# 6waydistro.net
KiCad netlist of a schematic drawn in EAGLE
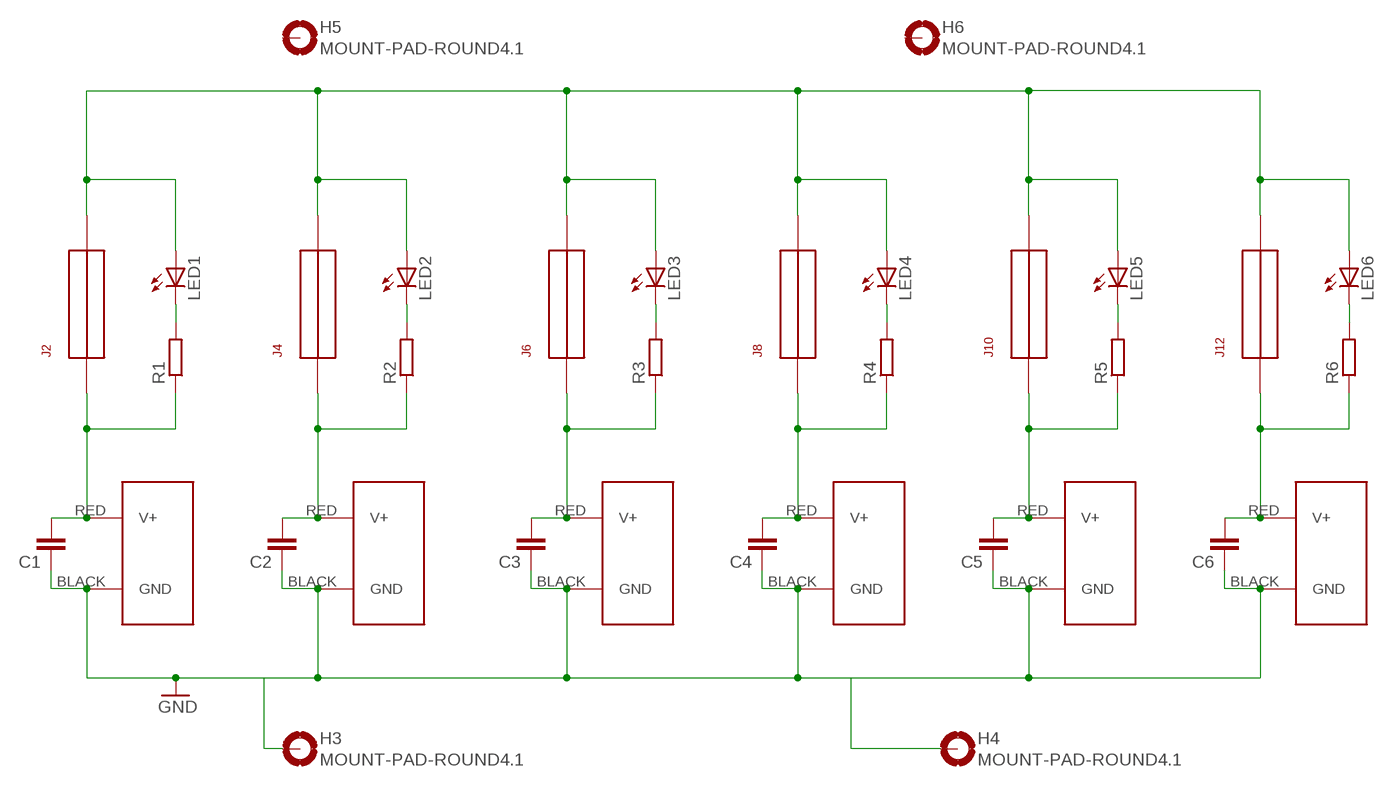
[diagram p0: schematic, sheet 1]

(export (version "E")
  (design (tool "Eeschema 10.0.6"))
  (components
    (comp (ref "C1")
      (value "C-EU050-025X075")
      (footprint "eagle-import:C050-025X075")
      (libsource (lib "eagle-import") (part "C-EU050-025X075"))
    )
    (comp (ref "C2")
      (value "C-EU050-025X075")
      (footprint "eagle-import:C050-025X075")
      (libsource (lib "eagle-import") (part "C-EU050-025X075"))
    )
    (comp (ref "C3")
      (value "C-EU050-025X075")
      (footprint "eagle-import:C050-025X075")
      (libsource (lib "eagle-import") (part "C-EU050-025X075"))
    )
    (comp (ref "C4")
      (value "C-EU050-025X075")
      (footprint "eagle-import:C050-025X075")
      (libsource (lib "eagle-import") (part "C-EU050-025X075"))
    )
    (comp (ref "C5")
      (value "C-EU050-025X075")
      (footprint "eagle-import:C050-025X075")
      (libsource (lib "eagle-import") (part "C-EU050-025X075"))
    )
    (comp (ref "C6")
      (value "C-EU050-025X075")
      (footprint "eagle-import:C050-025X075")
      (libsource (lib "eagle-import") (part "C-EU050-025X075"))
    )
    (comp (ref "H3")
      (value "MOUNT-PAD-ROUND4.1")
      (footprint "eagle-import:4,1-PAD")
      (libsource (lib "eagle-import") (part "MOUNT-PAD-ROUND4.1"))
    )
    (comp (ref "H4")
      (value "MOUNT-PAD-ROUND4.1")
      (footprint "eagle-import:4,1-PAD")
      (libsource (lib "eagle-import") (part "MOUNT-PAD-ROUND4.1"))
    )
    (comp (ref "H5")
      (value "MOUNT-PAD-ROUND4.1")
      (footprint "eagle-import:4,1-PAD")
      (libsource (lib "eagle-import") (part "MOUNT-PAD-ROUND4.1"))
    )
    (comp (ref "H6")
      (value "MOUNT-PAD-ROUND4.1")
      (footprint "eagle-import:4,1-PAD")
      (libsource (lib "eagle-import") (part "MOUNT-PAD-ROUND4.1"))
    )
    (comp (ref "J1")
      (value "POWERPOLE_POWER45A")
      (footprint "eagle-import:POWERPOLE_PAIR_45A")
      (libsource (lib "eagle-import") (part "POWERPOLE_POWER45A"))
    )
    (comp (ref "J2")
      (value "FUSEATC")
      (footprint "eagle-import:FUSE_ATC")
      (libsource (lib "eagle-import") (part "FUSEATC"))
    )
    (comp (ref "J3")
      (value "POWERPOLE_POWER45A")
      (footprint "eagle-import:POWERPOLE_PAIR_45A")
      (libsource (lib "eagle-import") (part "POWERPOLE_POWER45A"))
    )
    (comp (ref "J4")
      (value "FUSEATC")
      (footprint "eagle-import:FUSE_ATC")
      (libsource (lib "eagle-import") (part "FUSEATC"))
    )
    (comp (ref "J5")
      (value "POWERPOLE_POWER45A")
      (footprint "eagle-import:POWERPOLE_PAIR_45A")
      (libsource (lib "eagle-import") (part "POWERPOLE_POWER45A"))
    )
    (comp (ref "J6")
      (value "FUSEATC")
      (footprint "eagle-import:FUSE_ATC")
      (libsource (lib "eagle-import") (part "FUSEATC"))
    )
    (comp (ref "J7")
      (value "POWERPOLE_POWER45A")
      (footprint "eagle-import:POWERPOLE_PAIR_45A")
      (libsource (lib "eagle-import") (part "POWERPOLE_POWER45A"))
    )
    (comp (ref "J8")
      (value "FUSEATC")
      (footprint "eagle-import:FUSE_ATC")
      (libsource (lib "eagle-import") (part "FUSEATC"))
    )
    (comp (ref "J9")
      (value "POWERPOLE_POWER45A")
      (footprint "eagle-import:POWERPOLE_PAIR_45A")
      (libsource (lib "eagle-import") (part "POWERPOLE_POWER45A"))
    )
    (comp (ref "J10")
      (value "FUSEATC")
      (footprint "eagle-import:FUSE_ATC")
      (libsource (lib "eagle-import") (part "FUSEATC"))
    )
    (comp (ref "J11")
      (value "POWERPOLE_POWER45A")
      (footprint "eagle-import:POWERPOLE_PAIR_45A")
      (libsource (lib "eagle-import") (part "POWERPOLE_POWER45A"))
    )
    (comp (ref "J12")
      (value "FUSEATC")
      (footprint "eagle-import:FUSE_ATC")
      (libsource (lib "eagle-import") (part "FUSEATC"))
    )
    (comp (ref "LED1")
      (value "LED3MM")
      (footprint "eagle-import:LED3MM")
      (libsource (lib "eagle-import") (part "LED3MM"))
    )
    (comp (ref "LED2")
      (value "LED3MM")
      (footprint "eagle-import:LED3MM")
      (libsource (lib "eagle-import") (part "LED3MM"))
    )
    (comp (ref "LED3")
      (value "LED3MM")
      (footprint "eagle-import:LED3MM")
      (libsource (lib "eagle-import") (part "LED3MM"))
    )
    (comp (ref "LED4")
      (value "LED3MM")
      (footprint "eagle-import:LED3MM")
      (libsource (lib "eagle-import") (part "LED3MM"))
    )
    (comp (ref "LED5")
      (value "LED3MM")
      (footprint "eagle-import:LED3MM")
      (libsource (lib "eagle-import") (part "LED3MM"))
    )
    (comp (ref "LED6")
      (value "LED3MM")
      (footprint "eagle-import:LED3MM")
      (libsource (lib "eagle-import") (part "LED3MM"))
    )
    (comp (ref "R1")
      (value "R-EU_0204/7")
      (footprint "eagle-import:0204_7")
      (libsource (lib "eagle-import") (part "R-EU_0204/7"))
    )
    (comp (ref "R2")
      (value "R-EU_0204/7")
      (footprint "eagle-import:0204_7")
      (libsource (lib "eagle-import") (part "R-EU_0204/7"))
    )
    (comp (ref "R3")
      (value "R-EU_0204/7")
      (footprint "eagle-import:0204_7")
      (libsource (lib "eagle-import") (part "R-EU_0204/7"))
    )
    (comp (ref "R4")
      (value "R-EU_0204/7")
      (footprint "eagle-import:0204_7")
      (libsource (lib "eagle-import") (part "R-EU_0204/7"))
    )
    (comp (ref "R5")
      (value "R-EU_0204/7")
      (footprint "eagle-import:0204_7")
      (libsource (lib "eagle-import") (part "R-EU_0204/7"))
    )
    (comp (ref "R6")
      (value "R-EU_0204/7")
      (footprint "eagle-import:0204_7")
      (libsource (lib "eagle-import") (part "R-EU_0204/7"))
    )
  )
  (nets
    (net (code "1") (name "GND") (class "Default")
      (node (ref "C1") (pin "1") (pinfunction "1_1") (pintype "passive"))
      (node (ref "C2") (pin "1") (pinfunction "1_1") (pintype "passive"))
      (node (ref "C3") (pin "1") (pinfunction "1_1") (pintype "passive"))
      (node (ref "C4") (pin "1") (pinfunction "1_1") (pintype "passive"))
      (node (ref "C5") (pin "1") (pinfunction "1_1") (pintype "passive"))
      (node (ref "C6") (pin "1") (pinfunction "1_1") (pintype "passive"))
      (node (ref "H3") (pin "B4,1") (pinfunction "MOUNT_B4,1") (pintype "passive"))
      (node (ref "H4") (pin "B4,1") (pinfunction "MOUNT_B4,1") (pintype "passive"))
      (node (ref "J1") (pin "BLACK") (pinfunction "GND_BLACK") (pintype "power_in"))
      (node (ref "J11") (pin "BLACK") (pinfunction "GND_BLACK") (pintype "power_in"))
      (node (ref "J3") (pin "BLACK") (pinfunction "GND_BLACK") (pintype "power_in"))
      (node (ref "J5") (pin "BLACK") (pinfunction "GND_BLACK") (pintype "power_in"))
      (node (ref "J7") (pin "BLACK") (pinfunction "GND_BLACK") (pintype "power_in"))
      (node (ref "J9") (pin "BLACK") (pinfunction "GND_BLACK") (pintype "power_in"))
    )
    (net (code "2") (name "Net-(J1-V+)") (class "Default")
      (node (ref "C1") (pin "2") (pinfunction "2_2") (pintype "passive"))
      (node (ref "J1") (pin "RED") (pinfunction "V+_RED") (pintype "power_in"))
      (node (ref "J2") (pin "P$1") (pinfunction "P$1_P$1") (pintype "bidirectional"))
      (node (ref "J2") (pin "P$2") (pinfunction "P$1_P$2") (pintype "bidirectional"))
      (node (ref "R1") (pin "1") (pinfunction "1_1") (pintype "passive"))
    )
    (net (code "3") (name "Net-(J3-V+)") (class "Default")
      (node (ref "C2") (pin "2") (pinfunction "2_2") (pintype "passive"))
      (node (ref "J3") (pin "RED") (pinfunction "V+_RED") (pintype "power_in"))
      (node (ref "J4") (pin "P$1") (pinfunction "P$1_P$1") (pintype "bidirectional"))
      (node (ref "J4") (pin "P$2") (pinfunction "P$1_P$2") (pintype "bidirectional"))
      (node (ref "R2") (pin "1") (pinfunction "1_1") (pintype "passive"))
    )
    (net (code "4") (name "Net-(J5-V+)") (class "Default")
      (node (ref "C3") (pin "2") (pinfunction "2_2") (pintype "passive"))
      (node (ref "J5") (pin "RED") (pinfunction "V+_RED") (pintype "power_in"))
      (node (ref "J6") (pin "P$1") (pinfunction "P$1_P$1") (pintype "bidirectional"))
      (node (ref "J6") (pin "P$2") (pinfunction "P$1_P$2") (pintype "bidirectional"))
      (node (ref "R3") (pin "1") (pinfunction "1_1") (pintype "passive"))
    )
    (net (code "5") (name "Net-(J7-V+)") (class "Default")
      (node (ref "C4") (pin "2") (pinfunction "2_2") (pintype "passive"))
      (node (ref "J7") (pin "RED") (pinfunction "V+_RED") (pintype "power_in"))
      (node (ref "J8") (pin "P$1") (pinfunction "P$1_P$1") (pintype "bidirectional"))
      (node (ref "J8") (pin "P$2") (pinfunction "P$1_P$2") (pintype "bidirectional"))
      (node (ref "R4") (pin "1") (pinfunction "1_1") (pintype "passive"))
    )
    (net (code "6") (name "Net-(J9-V+)") (class "Default")
      (node (ref "C5") (pin "2") (pinfunction "2_2") (pintype "passive"))
      (node (ref "J10") (pin "P$1") (pinfunction "P$1_P$1") (pintype "bidirectional"))
      (node (ref "J10") (pin "P$2") (pinfunction "P$1_P$2") (pintype "bidirectional"))
      (node (ref "J9") (pin "RED") (pinfunction "V+_RED") (pintype "power_in"))
      (node (ref "R5") (pin "1") (pinfunction "1_1") (pintype "passive"))
    )
    (net (code "7") (name "Net-(J10-P$2-PadP$3)") (class "Default")
      (node (ref "J10") (pin "P$3") (pinfunction "P$2_P$3") (pintype "bidirectional"))
      (node (ref "J10") (pin "P$4") (pinfunction "P$2_P$4") (pintype "bidirectional"))
      (node (ref "J12") (pin "P$3") (pinfunction "P$2_P$3") (pintype "bidirectional"))
      (node (ref "J12") (pin "P$4") (pinfunction "P$2_P$4") (pintype "bidirectional"))
      (node (ref "J2") (pin "P$3") (pinfunction "P$2_P$3") (pintype "bidirectional"))
      (node (ref "J2") (pin "P$4") (pinfunction "P$2_P$4") (pintype "bidirectional"))
      (node (ref "J4") (pin "P$3") (pinfunction "P$2_P$3") (pintype "bidirectional"))
      (node (ref "J4") (pin "P$4") (pinfunction "P$2_P$4") (pintype "bidirectional"))
      (node (ref "J6") (pin "P$3") (pinfunction "P$2_P$3") (pintype "bidirectional"))
      (node (ref "J6") (pin "P$4") (pinfunction "P$2_P$4") (pintype "bidirectional"))
      (node (ref "J8") (pin "P$3") (pinfunction "P$2_P$3") (pintype "bidirectional"))
      (node (ref "J8") (pin "P$4") (pinfunction "P$2_P$4") (pintype "bidirectional"))
      (node (ref "LED1") (pin "A") (pinfunction "A_A") (pintype "passive"))
      (node (ref "LED2") (pin "A") (pinfunction "A_A") (pintype "passive"))
      (node (ref "LED3") (pin "A") (pinfunction "A_A") (pintype "passive"))
      (node (ref "LED4") (pin "A") (pinfunction "A_A") (pintype "passive"))
      (node (ref "LED5") (pin "A") (pinfunction "A_A") (pintype "passive"))
      (node (ref "LED6") (pin "A") (pinfunction "A_A") (pintype "passive"))
    )
    (net (code "8") (name "Net-(J11-V+)") (class "Default")
      (node (ref "C6") (pin "2") (pinfunction "2_2") (pintype "passive"))
      (node (ref "J11") (pin "RED") (pinfunction "V+_RED") (pintype "power_in"))
      (node (ref "J12") (pin "P$1") (pinfunction "P$1_P$1") (pintype "bidirectional"))
      (node (ref "J12") (pin "P$2") (pinfunction "P$1_P$2") (pintype "bidirectional"))
      (node (ref "R6") (pin "1") (pinfunction "1_1") (pintype "passive"))
    )
    (net (code "9") (name "Net-(LED1-C)") (class "Default")
      (node (ref "LED1") (pin "K") (pinfunction "C_K") (pintype "passive"))
      (node (ref "R1") (pin "2") (pinfunction "2_2") (pintype "passive"))
    )
    (net (code "10") (name "Net-(LED2-C)") (class "Default")
      (node (ref "LED2") (pin "K") (pinfunction "C_K") (pintype "passive"))
      (node (ref "R2") (pin "2") (pinfunction "2_2") (pintype "passive"))
    )
    (net (code "11") (name "Net-(LED3-C)") (class "Default")
      (node (ref "LED3") (pin "K") (pinfunction "C_K") (pintype "passive"))
      (node (ref "R3") (pin "2") (pinfunction "2_2") (pintype "passive"))
    )
    (net (code "12") (name "Net-(LED4-C)") (class "Default")
      (node (ref "LED4") (pin "K") (pinfunction "C_K") (pintype "passive"))
      (node (ref "R4") (pin "2") (pinfunction "2_2") (pintype "passive"))
    )
    (net (code "13") (name "Net-(LED5-C)") (class "Default")
      (node (ref "LED5") (pin "K") (pinfunction "C_K") (pintype "passive"))
      (node (ref "R5") (pin "2") (pinfunction "2_2") (pintype "passive"))
    )
    (net (code "14") (name "Net-(LED6-C)") (class "Default")
      (node (ref "LED6") (pin "K") (pinfunction "C_K") (pintype "passive"))
      (node (ref "R6") (pin "2") (pinfunction "2_2") (pintype "passive"))
    )
    (net (code "15") (name "unconnected-(H5-MOUNT-PadB4,1)") (class "Default")
      (node (ref "H5") (pin "B4,1") (pinfunction "MOUNT_B4,1") (pintype "passive"))
    )
    (net (code "16") (name "unconnected-(H6-MOUNT-PadB4,1)") (class "Default")
      (node (ref "H6") (pin "B4,1") (pinfunction "MOUNT_B4,1") (pintype "passive"))
    )
  )
)
